# speaker.net
KiCad netlist of a schematic drawn in EAGLE
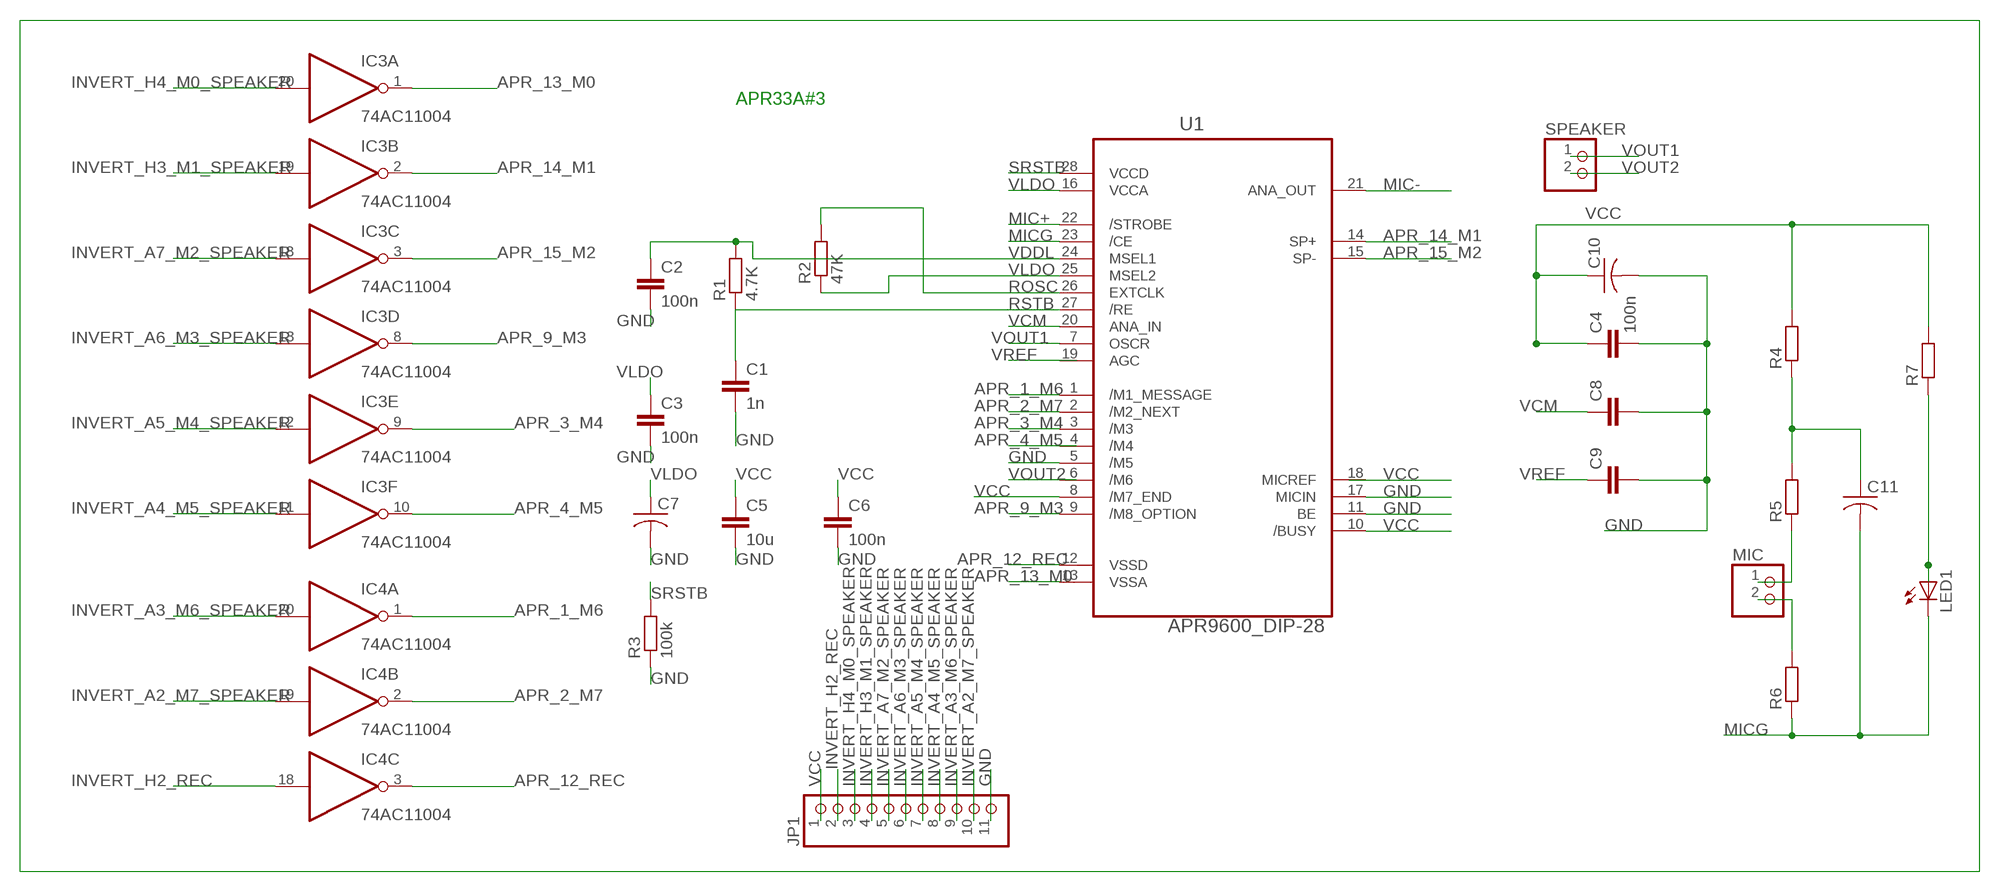
[diagram p0: schematic, sheet 1]

(export (version "E")
  (design (tool "Eeschema 10.0.6"))
  (components
    (comp (ref "C1")
      (value "1n")
      (footprint "eagle-import:C1206")
      (libsource (lib "eagle-import") (part "C-EUC1206"))
    )
    (comp (ref "C2")
      (value "100n")
      (footprint "eagle-import:C1206")
      (libsource (lib "eagle-import") (part "C-EUC1206"))
    )
    (comp (ref "C3")
      (value "100n")
      (footprint "eagle-import:C1206")
      (libsource (lib "eagle-import") (part "C-EUC1206"))
    )
    (comp (ref "C4")
      (value "100n")
      (footprint "eagle-import:C1206")
      (libsource (lib "eagle-import") (part "C-EUC1206"))
    )
    (comp (ref "C5")
      (value "10u")
      (footprint "eagle-import:C1206")
      (libsource (lib "eagle-import") (part "C-EUC1206"))
    )
    (comp (ref "C6")
      (value "100n")
      (footprint "eagle-import:C1206")
      (libsource (lib "eagle-import") (part "C-EUC1206"))
    )
    (comp (ref "C7")
      (value "C-US025-050X050")
      (footprint "eagle-import:C025-050X050")
      (libsource (lib "eagle-import") (part "C-US025-050X050"))
    )
    (comp (ref "C8")
      (value "C-EUC1206")
      (footprint "eagle-import:C1206")
      (libsource (lib "eagle-import") (part "C-EUC1206"))
    )
    (comp (ref "C9")
      (value "C-EUC1206")
      (footprint "eagle-import:C1206")
      (libsource (lib "eagle-import") (part "C-EUC1206"))
    )
    (comp (ref "C10")
      (value "C-US025-050X050")
      (footprint "eagle-import:C025-050X050")
      (libsource (lib "eagle-import") (part "C-US025-050X050"))
    )
    (comp (ref "C11")
      (value "C-US025-050X050")
      (footprint "eagle-import:C025-050X050")
      (libsource (lib "eagle-import") (part "C-US025-050X050"))
    )
    (comp (ref "IC3")
      (value "74AC11004")
      (footprint "eagle-import:DIL20")
      (libsource (lib "eagle-import") (part "74AC11004"))
    )
    (comp (ref "IC4")
      (value "74AC11004")
      (footprint "eagle-import:DIL20")
      (libsource (lib "eagle-import") (part "74AC11004"))
    )
    (comp (ref "JP1")
      (value "PINHD-1X11")
      (footprint "eagle-import:1X11")
      (libsource (lib "eagle-import") (part "PINHD-1X11"))
    )
    (comp (ref "LED1")
      (value "LEDSMT1206")
      (footprint "eagle-import:1206")
      (libsource (lib "eagle-import") (part "LEDSMT1206"))
    )
    (comp (ref "MIC")
      (value "PINHD-1X2")
      (footprint "eagle-import:1X02")
      (libsource (lib "eagle-import") (part "PINHD-1X2"))
    )
    (comp (ref "R1")
      (value "4.7K")
      (footprint "eagle-import:M1206")
      (libsource (lib "eagle-import") (part "R-EU_M1206"))
    )
    (comp (ref "R2")
      (value "47K")
      (footprint "eagle-import:M1206")
      (libsource (lib "eagle-import") (part "R-EU_M1206"))
    )
    (comp (ref "R3")
      (value "100k")
      (footprint "eagle-import:M1206")
      (libsource (lib "eagle-import") (part "R-EU_M1206"))
    )
    (comp (ref "R4")
      (value "R-EU_R1206")
      (footprint "eagle-import:R1206")
      (libsource (lib "eagle-import") (part "resistor_348_R-EU_R1206"))
    )
    (comp (ref "R5")
      (value "R-EU_R1206")
      (footprint "eagle-import:R1206")
      (libsource (lib "eagle-import") (part "resistor_348_R-EU_R1206"))
    )
    (comp (ref "R6")
      (value "R-EU_R1206")
      (footprint "eagle-import:R1206")
      (libsource (lib "eagle-import") (part "resistor_348_R-EU_R1206"))
    )
    (comp (ref "R7")
      (value "R-EU_R1206")
      (footprint "eagle-import:R1206")
      (libsource (lib "eagle-import") (part "resistor_348_R-EU_R1206"))
    )
    (comp (ref "SPEAKER")
      (value "PINHD-1X2")
      (footprint "eagle-import:1X02")
      (libsource (lib "eagle-import") (part "PINHD-1X2"))
    )
    (comp (ref "U1")
      (value "APR9600_DIP-28")
      (footprint "eagle-import:DIP254P1525X550-28P")
      (libsource (lib "eagle-import") (part "APR9600_DIP-28"))
    )
  )
  (nets
    (net (code "1") (name "/APR_1_M6") (class "Default")
      (node (ref "IC4") (pin "1") (pinfunction "O_1") (pintype "output"))
      (node (ref "U1") (pin "1") (pinfunction "/M1_MESSAGE_1") (pintype "input"))
    )
    (net (code "2") (name "/APR_2_M7") (class "Default")
      (node (ref "IC4") (pin "2") (pinfunction "O_2") (pintype "output"))
      (node (ref "U1") (pin "2") (pinfunction "/M2_NEXT_2") (pintype "input"))
    )
    (net (code "3") (name "/APR_3_M4") (class "Default")
      (node (ref "IC3") (pin "9") (pinfunction "O_9") (pintype "output"))
      (node (ref "U1") (pin "3") (pinfunction "/M3_3") (pintype "input"))
    )
    (net (code "4") (name "/APR_4_M5") (class "Default")
      (node (ref "IC3") (pin "10") (pinfunction "O_10") (pintype "output"))
    )
    (net (code "5") (name "/APR_9_M3") (class "Default")
      (node (ref "IC3") (pin "8") (pinfunction "O_8") (pintype "output"))
      (node (ref "U1") (pin "9") (pinfunction "/M8_OPTION_9") (pintype "input"))
    )
    (net (code "6") (name "/APR_12_REC") (class "Default")
      (node (ref "IC4") (pin "3") (pinfunction "O_3") (pintype "output"))
      (node (ref "U1") (pin "12") (pinfunction "VSSD_12") (pintype "passive"))
    )
    (net (code "7") (name "/APR_13_M0") (class "Default")
      (node (ref "IC3") (pin "1") (pinfunction "O_1") (pintype "output"))
      (node (ref "U1") (pin "13") (pinfunction "VSSA_13") (pintype "passive"))
    )
    (net (code "8") (name "/APR_14_M1") (class "Default")
      (node (ref "IC3") (pin "2") (pinfunction "O_2") (pintype "output"))
      (node (ref "U1") (pin "14") (pinfunction "SP+_14") (pintype "output"))
    )
    (net (code "9") (name "/APR_15_M2") (class "Default")
      (node (ref "IC3") (pin "3") (pinfunction "O_3") (pintype "output"))
      (node (ref "U1") (pin "15") (pinfunction "SP-_15") (pintype "output"))
    )
    (net (code "10") (name "/GND") (class "Default")
      (node (ref "C1") (pin "2") (pinfunction "2_2") (pintype "passive"))
      (node (ref "C10") (pin "2") (pinfunction "2_2") (pintype "passive"))
      (node (ref "C2") (pin "2") (pinfunction "2_2") (pintype "passive"))
      (node (ref "C3") (pin "2") (pinfunction "2_2") (pintype "passive"))
      (node (ref "C4") (pin "2") (pinfunction "2_2") (pintype "passive"))
      (node (ref "C5") (pin "2") (pinfunction "2_2") (pintype "passive"))
      (node (ref "C6") (pin "2") (pinfunction "2_2") (pintype "passive"))
      (node (ref "C7") (pin "2") (pinfunction "2_2") (pintype "passive"))
      (node (ref "C8") (pin "2") (pinfunction "2_2") (pintype "passive"))
      (node (ref "C9") (pin "2") (pinfunction "2_2") (pintype "passive"))
      (node (ref "JP1") (pin "11") (pinfunction "11_11") (pintype "passive"))
      (node (ref "R3") (pin "1") (pinfunction "1_1") (pintype "passive"))
      (node (ref "U1") (pin "11") (pinfunction "BE_11") (pintype "input"))
      (node (ref "U1") (pin "17") (pinfunction "MICIN_17") (pintype "input"))
      (node (ref "U1") (pin "5") (pinfunction "/M5_5") (pintype "input"))
    )
    (net (code "11") (name "/INVERT_A2_M7_SPEAKER") (class "Default")
      (node (ref "IC4") (pin "19") (pinfunction "I_19") (pintype "input"))
      (node (ref "JP1") (pin "10") (pinfunction "10_10") (pintype "passive"))
    )
    (net (code "12") (name "/INVERT_A3_M6_SPEAKER") (class "Default")
      (node (ref "IC4") (pin "20") (pinfunction "I_20") (pintype "input"))
      (node (ref "JP1") (pin "9") (pinfunction "9_9") (pintype "passive"))
    )
    (net (code "13") (name "/INVERT_A4_M5_SPEAKER") (class "Default")
      (node (ref "IC3") (pin "11") (pinfunction "I_11") (pintype "input"))
      (node (ref "JP1") (pin "8") (pinfunction "8_8") (pintype "passive"))
    )
    (net (code "14") (name "/INVERT_A5_M4_SPEAKER") (class "Default")
      (node (ref "IC3") (pin "12") (pinfunction "I_12") (pintype "input"))
      (node (ref "JP1") (pin "7") (pinfunction "7_7") (pintype "passive"))
    )
    (net (code "15") (name "/INVERT_A6_M3_SPEAKER") (class "Default")
      (node (ref "IC3") (pin "13") (pinfunction "I_13") (pintype "input"))
      (node (ref "JP1") (pin "6") (pinfunction "6_6") (pintype "passive"))
    )
    (net (code "16") (name "/INVERT_A7_M2_SPEAKER") (class "Default")
      (node (ref "IC3") (pin "18") (pinfunction "I_18") (pintype "input"))
      (node (ref "JP1") (pin "5") (pinfunction "5_5") (pintype "passive"))
    )
    (net (code "17") (name "/INVERT_H2_REC") (class "Default")
      (node (ref "IC4") (pin "18") (pinfunction "I_18") (pintype "input"))
      (node (ref "JP1") (pin "2") (pinfunction "2_2") (pintype "passive"))
    )
    (net (code "18") (name "/INVERT_H3_M1_SPEAKER") (class "Default")
      (node (ref "IC3") (pin "19") (pinfunction "I_19") (pintype "input"))
      (node (ref "JP1") (pin "4") (pinfunction "4_4") (pintype "passive"))
    )
    (net (code "19") (name "/INVERT_H4_M0_SPEAKER") (class "Default")
      (node (ref "IC3") (pin "20") (pinfunction "I_20") (pintype "input"))
      (node (ref "JP1") (pin "3") (pinfunction "3_3") (pintype "passive"))
    )
    (net (code "20") (name "/MIC+") (class "Default")
      (node (ref "U1") (pin "22") (pinfunction "/STROBE_22") (pintype "input"))
    )
    (net (code "21") (name "/MIC-") (class "Default")
      (node (ref "U1") (pin "21") (pinfunction "ANA_OUT_21") (pintype "output"))
    )
    (net (code "22") (name "/MICG") (class "Default")
      (node (ref "C11") (pin "2") (pinfunction "2_2") (pintype "passive"))
      (node (ref "LED1") (pin "C") (pinfunction "C_C") (pintype "passive"))
      (node (ref "R6") (pin "1") (pinfunction "1_1") (pintype "passive"))
      (node (ref "U1") (pin "23") (pinfunction "/CE_23") (pintype "input"))
    )
    (net (code "23") (name "/ROSC") (class "Default")
      (node (ref "R2") (pin "2") (pinfunction "2_2") (pintype "passive"))
      (node (ref "U1") (pin "26") (pinfunction "EXTCLK_26") (pintype "input"))
    )
    (net (code "24") (name "/RSTB") (class "Default")
      (node (ref "C1") (pin "1") (pinfunction "1_1") (pintype "passive"))
      (node (ref "R1") (pin "1") (pinfunction "1_1") (pintype "passive"))
      (node (ref "U1") (pin "27") (pinfunction "/RE_27") (pintype "input"))
    )
    (net (code "25") (name "/SRSTB") (class "Default")
      (node (ref "R3") (pin "2") (pinfunction "2_2") (pintype "passive"))
      (node (ref "U1") (pin "28") (pinfunction "VCCD_28") (pintype "power_in"))
    )
    (net (code "26") (name "/VCC") (class "Default")
      (node (ref "C10") (pin "1") (pinfunction "1_1") (pintype "passive"))
      (node (ref "C4") (pin "1") (pinfunction "1_1") (pintype "passive"))
      (node (ref "C5") (pin "1") (pinfunction "1_1") (pintype "passive"))
      (node (ref "C6") (pin "1") (pinfunction "1_1") (pintype "passive"))
      (node (ref "JP1") (pin "1") (pinfunction "1_1") (pintype "passive"))
      (node (ref "R4") (pin "2") (pinfunction "2_2") (pintype "passive"))
      (node (ref "R7") (pin "2") (pinfunction "2_2") (pintype "passive"))
      (node (ref "U1") (pin "10") (pinfunction "/BUSY_10") (pintype "input"))
      (node (ref "U1") (pin "8") (pinfunction "/M7_END_8") (pintype "input"))
    )
    (net (code "27") (name "/VCM") (class "Default")
      (node (ref "C8") (pin "1") (pinfunction "1_1") (pintype "passive"))
      (node (ref "U1") (pin "20") (pinfunction "ANA_IN_20") (pintype "input"))
    )
    (net (code "28") (name "/VDDL") (class "Default")
      (node (ref "C2") (pin "1") (pinfunction "1_1") (pintype "passive"))
      (node (ref "R1") (pin "2") (pinfunction "2_2") (pintype "passive"))
      (node (ref "U1") (pin "24") (pinfunction "MSEL1_24") (pintype "input"))
    )
    (net (code "29") (name "/VLDO") (class "Default")
      (node (ref "C3") (pin "1") (pinfunction "1_1") (pintype "passive"))
      (node (ref "C7") (pin "1") (pinfunction "1_1") (pintype "passive"))
      (node (ref "R2") (pin "1") (pinfunction "1_1") (pintype "passive"))
      (node (ref "U1") (pin "16") (pinfunction "VCCA_16") (pintype "power_in"))
      (node (ref "U1") (pin "25") (pinfunction "MSEL2_25") (pintype "input"))
    )
    (net (code "30") (name "/VOUT1") (class "Default")
      (node (ref "SPEAKER") (pin "1") (pinfunction "1_1") (pintype "passive"))
      (node (ref "U1") (pin "7") (pinfunction "OSCR_7") (pintype "input"))
    )
    (net (code "31") (name "/VOUT2") (class "Default")
      (node (ref "SPEAKER") (pin "2") (pinfunction "2_2") (pintype "passive"))
    )
    (net (code "32") (name "/VREF") (class "Default")
      (node (ref "C9") (pin "1") (pinfunction "1_1") (pintype "passive"))
    )
    (net (code "33") (name "Net-(C11-Pad1)") (class "Default")
      (node (ref "C11") (pin "1") (pinfunction "1_1") (pintype "passive"))
      (node (ref "R4") (pin "1") (pinfunction "1_1") (pintype "passive"))
      (node (ref "R5") (pin "2") (pinfunction "2_2") (pintype "passive"))
    )
    (net (code "34") (name "Net-(LED1-PadA)") (class "Default")
      (node (ref "LED1") (pin "A") (pinfunction "A_A") (pintype "passive"))
      (node (ref "R7") (pin "1") (pinfunction "1_1") (pintype "passive"))
    )
    (net (code "35") (name "Net-(MIC-Pad1)") (class "Default")
      (node (ref "MIC") (pin "1") (pinfunction "1_1") (pintype "passive"))
      (node (ref "R5") (pin "1") (pinfunction "1_1") (pintype "passive"))
    )
    (net (code "36") (name "Net-(MIC-Pad2)") (class "Default")
      (node (ref "MIC") (pin "2") (pinfunction "2_2") (pintype "passive"))
      (node (ref "R6") (pin "2") (pinfunction "2_2") (pintype "passive"))
    )
    (net (code "37") (name "unconnected-(U1-AGC-Pad19)") (class "Default")
      (node (ref "U1") (pin "19") (pinfunction "AGC_19") (pintype "input"))
    )
    (net (code "38") (name "unconnected-(U1-MICREF-Pad18)") (class "Default")
      (node (ref "U1") (pin "18") (pinfunction "MICREF_18") (pintype "input"))
    )
    (net (code "39") (name "unconnected-(U1-{slash}M4-Pad4)") (class "Default")
      (node (ref "U1") (pin "4") (pinfunction "/M4_4") (pintype "input"))
    )
    (net (code "40") (name "unconnected-(U1-{slash}M6-Pad6)") (class "Default")
      (node (ref "U1") (pin "6") (pinfunction "/M6_6") (pintype "input"))
    )
  )
)
